# CONNECTEUR_1.net
KiCad netlist of a schematic drawn in Altium Designer
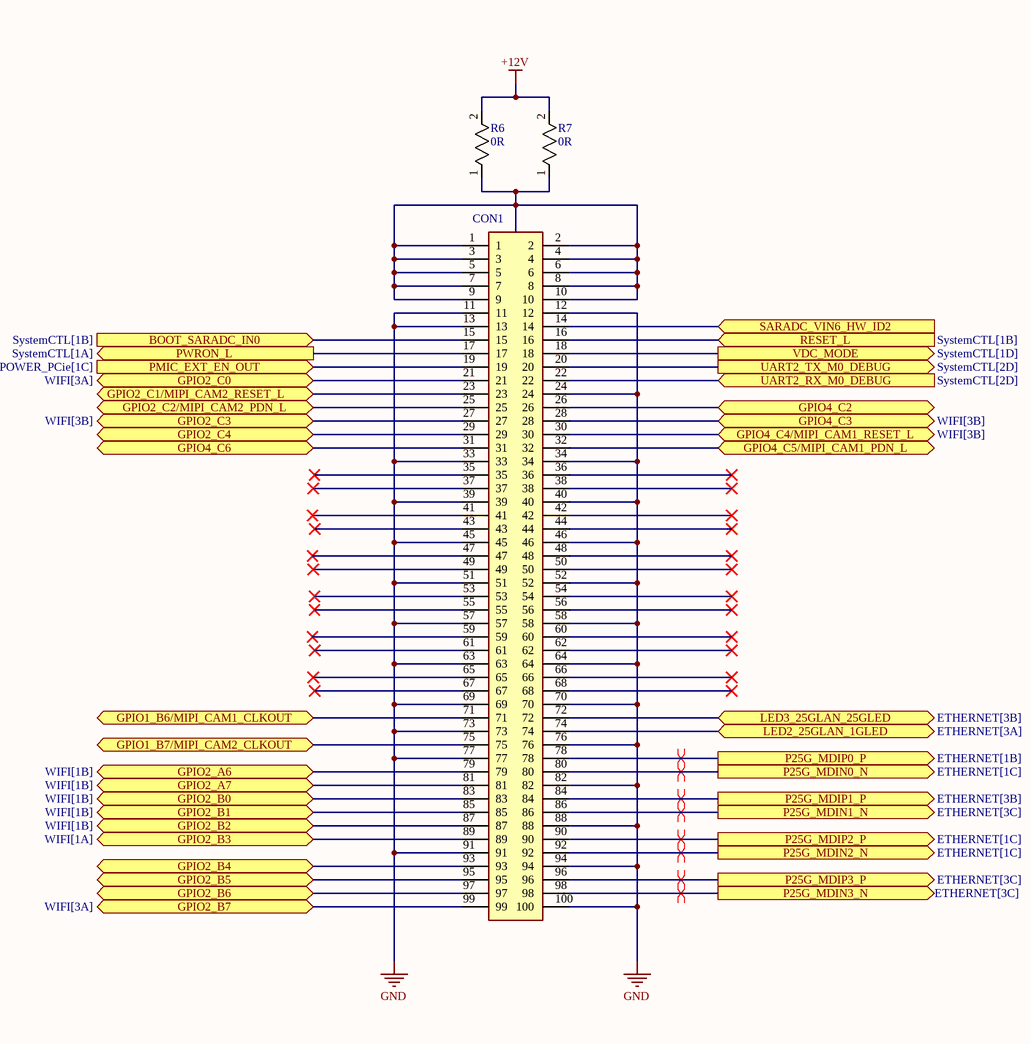
[diagram p0: CONNECTEUR_1.SchDoc, right]

(export (version "E")
  (design (tool "Eeschema 10.0.6"))
  (components
    (comp (ref "CON1")
      (value "DF40HC")
      (footprint "SamacSys:DF40HC30100DS04V51")
      (description "Stacking Board Connector, DF40 Series, Receptacle, 0.4 mm, 100, Surface Mount, G")
      (fields
        (field (name "MANUFACTURER_PART_NUMBER") "DF40HC(3.0)-100DS-0.4V(51")
        (field (name "MOUSER PART NUMBER") "798-DF40HC30100DS451")
      )
      (libsource (lib "SamacSys") (part "DF40HC(3.0)-100DS-0.4V(51)"))
    )
    (comp (ref "R6")
      (value "0R")
      (footprint "SamacSys:ERJ3EKF1000V")
      (description "Zero Ohm Resistor, Jumper, 0603 [1608 Metric], Thick Film, 100 mW, 1 A, Surface Mount")
      (fields
        (field (name "MANUFACTURER_PART_NUMBER") "ERJ-3GEY0R00V")
        (field (name "MOUSER PART NUMBER") "667-ERJ-3GEY0R00V")
      )
      (libsource (lib "SamacSys") (part "ERJ-3GEY0R00V"))
    )
    (comp (ref "R7")
      (value "0R")
      (footprint "SamacSys:ERJ3EKF1000V")
      (description "Zero Ohm Resistor, Jumper, 0603 [1608 Metric], Thick Film, 100 mW, 1 A, Surface Mount")
      (fields
        (field (name "MANUFACTURER_PART_NUMBER") "ERJ-3GEY0R00V")
        (field (name "MOUSER PART NUMBER") "667-ERJ-3GEY0R00V")
      )
      (libsource (lib "SamacSys") (part "ERJ-3GEY0R00V"))
    )
  )
  (nets
    (net (code "1") (name "+12V") (class "Default")
      (node (ref "R6") (pin "2") (pinfunction "2_2") (pintype "passive"))
      (node (ref "R7") (pin "2") (pinfunction "2_2") (pintype "passive"))
    )
    (net (code "2") (name "/BOOT_SARADC_IN0") (class "Default")
      (node (ref "CON1") (pin "15") (pinfunction "15_15") (pintype "passive"))
    )
    (net (code "3") (name "/GPIO1_B6{slash}MIPI_CAM1_CLKOUT") (class "Default")
      (node (ref "CON1") (pin "71") (pinfunction "71_71") (pintype "passive"))
    )
    (net (code "4") (name "/GPIO1_B7{slash}MIPI_CAM2_CLKOUT") (class "Default")
      (node (ref "CON1") (pin "75") (pinfunction "75_75") (pintype "passive"))
    )
    (net (code "5") (name "/GPIO2_A6") (class "Default")
      (node (ref "CON1") (pin "79") (pinfunction "79_79") (pintype "passive"))
    )
    (net (code "6") (name "/GPIO2_A7") (class "Default")
      (node (ref "CON1") (pin "81") (pinfunction "81_81") (pintype "passive"))
    )
    (net (code "7") (name "/GPIO2_B0") (class "Default")
      (node (ref "CON1") (pin "83") (pinfunction "83_83") (pintype "passive"))
    )
    (net (code "8") (name "/GPIO2_B1") (class "Default")
      (node (ref "CON1") (pin "85") (pinfunction "85_85") (pintype "passive"))
    )
    (net (code "9") (name "/GPIO2_B2") (class "Default")
      (node (ref "CON1") (pin "87") (pinfunction "87_87") (pintype "passive"))
    )
    (net (code "10") (name "/GPIO2_B3") (class "Default")
      (node (ref "CON1") (pin "89") (pinfunction "89_89") (pintype "passive"))
    )
    (net (code "11") (name "/GPIO2_B4") (class "Default")
      (node (ref "CON1") (pin "93") (pinfunction "93_93") (pintype "passive"))
    )
    (net (code "12") (name "/GPIO2_B5") (class "Default")
      (node (ref "CON1") (pin "95") (pinfunction "95_95") (pintype "passive"))
    )
    (net (code "13") (name "/GPIO2_B6") (class "Default")
      (node (ref "CON1") (pin "97") (pinfunction "97_97") (pintype "passive"))
    )
    (net (code "14") (name "/GPIO2_B7") (class "Default")
      (node (ref "CON1") (pin "99") (pinfunction "99_99") (pintype "passive"))
    )
    (net (code "15") (name "/GPIO2_C0") (class "Default")
      (node (ref "CON1") (pin "21") (pinfunction "21_21") (pintype "passive"))
    )
    (net (code "16") (name "/GPIO2_C1{slash}MIPI_CAM2_RESET_L") (class "Default")
      (node (ref "CON1") (pin "23") (pinfunction "23_23") (pintype "passive"))
    )
    (net (code "17") (name "/GPIO2_C2{slash}MIPI_CAM2_PDN_L") (class "Default")
      (node (ref "CON1") (pin "25") (pinfunction "25_25") (pintype "passive"))
    )
    (net (code "18") (name "/GPIO2_C3") (class "Default")
      (node (ref "CON1") (pin "27") (pinfunction "27_27") (pintype "passive"))
    )
    (net (code "19") (name "/GPIO2_C4") (class "Default")
      (node (ref "CON1") (pin "29") (pinfunction "29_29") (pintype "passive"))
    )
    (net (code "20") (name "/GPIO4_C2") (class "Default")
      (node (ref "CON1") (pin "26") (pinfunction "26_26") (pintype "passive"))
    )
    (net (code "21") (name "/GPIO4_C3") (class "Default")
      (node (ref "CON1") (pin "28") (pinfunction "28_28") (pintype "passive"))
    )
    (net (code "22") (name "/GPIO4_C4{slash}MIPI_CAM1_RESET_L") (class "Default")
      (node (ref "CON1") (pin "30") (pinfunction "30_30") (pintype "passive"))
    )
    (net (code "23") (name "/GPIO4_C5{slash}MIPI_CAM1_PDN_L") (class "Default")
      (node (ref "CON1") (pin "32") (pinfunction "32_32") (pintype "passive"))
    )
    (net (code "24") (name "/GPIO4_C6") (class "Default")
      (node (ref "CON1") (pin "31") (pinfunction "31_31") (pintype "passive"))
    )
    (net (code "25") (name "/LED2_25GLAN_1GLED") (class "Default")
      (node (ref "CON1") (pin "74") (pinfunction "74_74") (pintype "passive"))
    )
    (net (code "26") (name "/LED3_25GLAN_25GLED") (class "Default")
      (node (ref "CON1") (pin "72") (pinfunction "72_72") (pintype "passive"))
    )
    (net (code "27") (name "/P25G_MDIN0_N") (class "Default")
      (node (ref "CON1") (pin "80") (pinfunction "80_80") (pintype "passive"))
    )
    (net (code "28") (name "/P25G_MDIN1_N") (class "Default")
      (node (ref "CON1") (pin "86") (pinfunction "86_86") (pintype "passive"))
    )
    (net (code "29") (name "/P25G_MDIN2_N") (class "Default")
      (node (ref "CON1") (pin "92") (pinfunction "92_92") (pintype "passive"))
    )
    (net (code "30") (name "/P25G_MDIN3_N") (class "Default")
      (node (ref "CON1") (pin "98") (pinfunction "98_98") (pintype "passive"))
    )
    (net (code "31") (name "/P25G_MDIP0_P") (class "Default")
      (node (ref "CON1") (pin "78") (pinfunction "78_78") (pintype "passive"))
    )
    (net (code "32") (name "/P25G_MDIP1_P") (class "Default")
      (node (ref "CON1") (pin "84") (pinfunction "84_84") (pintype "passive"))
    )
    (net (code "33") (name "/P25G_MDIP2_P") (class "Default")
      (node (ref "CON1") (pin "90") (pinfunction "90_90") (pintype "passive"))
    )
    (net (code "34") (name "/P25G_MDIP3_P") (class "Default")
      (node (ref "CON1") (pin "96") (pinfunction "96_96") (pintype "passive"))
    )
    (net (code "35") (name "/PMIC_EXT_EN_OUT") (class "Default")
      (node (ref "CON1") (pin "19") (pinfunction "19_19") (pintype "passive"))
    )
    (net (code "36") (name "/PWRON_L") (class "Default")
      (node (ref "CON1") (pin "17") (pinfunction "17_17") (pintype "passive"))
    )
    (net (code "37") (name "/RESET_L") (class "Default")
      (node (ref "CON1") (pin "16") (pinfunction "16_16") (pintype "passive"))
    )
    (net (code "38") (name "/SARADC_VIN6_HW_ID2") (class "Default")
      (node (ref "CON1") (pin "14") (pinfunction "14_14") (pintype "passive"))
    )
    (net (code "39") (name "/UART2_RX_M0_DEBUG") (class "Default")
      (node (ref "CON1") (pin "22") (pinfunction "22_22") (pintype "passive"))
    )
    (net (code "40") (name "/UART2_TX_M0_DEBUG") (class "Default")
      (node (ref "CON1") (pin "20") (pinfunction "20_20") (pintype "passive"))
    )
    (net (code "41") (name "/VDC_MODE") (class "Default")
      (node (ref "CON1") (pin "18") (pinfunction "18_18") (pintype "passive"))
    )
    (net (code "42") (name "GND") (class "Default")
      (node (ref "CON1") (pin "100") (pinfunction "100_100") (pintype "passive"))
      (node (ref "CON1") (pin "11") (pinfunction "11_11") (pintype "passive"))
      (node (ref "CON1") (pin "12") (pinfunction "12_12") (pintype "passive"))
      (node (ref "CON1") (pin "13") (pinfunction "13_13") (pintype "passive"))
      (node (ref "CON1") (pin "24") (pinfunction "24_24") (pintype "passive"))
      (node (ref "CON1") (pin "33") (pinfunction "33_33") (pintype "passive"))
      (node (ref "CON1") (pin "34") (pinfunction "34_34") (pintype "passive"))
      (node (ref "CON1") (pin "39") (pinfunction "39_39") (pintype "passive"))
      (node (ref "CON1") (pin "40") (pinfunction "40_40") (pintype "passive"))
      (node (ref "CON1") (pin "45") (pinfunction "45_45") (pintype "passive"))
      (node (ref "CON1") (pin "46") (pinfunction "46_46") (pintype "passive"))
      (node (ref "CON1") (pin "51") (pinfunction "51_51") (pintype "passive"))
      (node (ref "CON1") (pin "52") (pinfunction "52_52") (pintype "passive"))
      (node (ref "CON1") (pin "57") (pinfunction "57_57") (pintype "passive"))
      (node (ref "CON1") (pin "58") (pinfunction "58_58") (pintype "passive"))
      (node (ref "CON1") (pin "63") (pinfunction "63_63") (pintype "passive"))
      (node (ref "CON1") (pin "64") (pinfunction "64_64") (pintype "passive"))
      (node (ref "CON1") (pin "69") (pinfunction "69_69") (pintype "passive"))
      (node (ref "CON1") (pin "70") (pinfunction "70_70") (pintype "passive"))
      (node (ref "CON1") (pin "73") (pinfunction "73_73") (pintype "passive"))
      (node (ref "CON1") (pin "76") (pinfunction "76_76") (pintype "passive"))
      (node (ref "CON1") (pin "77") (pinfunction "77_77") (pintype "passive"))
      (node (ref "CON1") (pin "82") (pinfunction "82_82") (pintype "passive"))
      (node (ref "CON1") (pin "88") (pinfunction "88_88") (pintype "passive"))
      (node (ref "CON1") (pin "91") (pinfunction "91_91") (pintype "passive"))
      (node (ref "CON1") (pin "94") (pinfunction "94_94") (pintype "passive"))
    )
    (net (code "43") (name "Net-(CON1-Pad1)") (class "Default")
      (node (ref "CON1") (pin "1") (pinfunction "1_1") (pintype "passive"))
      (node (ref "CON1") (pin "10") (pinfunction "10_10") (pintype "passive"))
      (node (ref "CON1") (pin "2") (pinfunction "2_2") (pintype "passive"))
      (node (ref "CON1") (pin "3") (pinfunction "3_3") (pintype "passive"))
      (node (ref "CON1") (pin "4") (pinfunction "4_4") (pintype "passive"))
      (node (ref "CON1") (pin "5") (pinfunction "5_5") (pintype "passive"))
      (node (ref "CON1") (pin "6") (pinfunction "6_6") (pintype "passive"))
      (node (ref "CON1") (pin "7") (pinfunction "7_7") (pintype "passive"))
      (node (ref "CON1") (pin "8") (pinfunction "8_8") (pintype "passive"))
      (node (ref "CON1") (pin "9") (pinfunction "9_9") (pintype "passive"))
      (node (ref "R6") (pin "1") (pinfunction "1_1") (pintype "passive"))
      (node (ref "R7") (pin "1") (pinfunction "1_1") (pintype "passive"))
    )
    (net (code "44") (name "unconnected-(CON1-Pad35)") (class "Default")
      (node (ref "CON1") (pin "35") (pinfunction "35_35") (pintype "passive+no_connect"))
    )
    (net (code "45") (name "unconnected-(CON1-Pad36)") (class "Default")
      (node (ref "CON1") (pin "36") (pinfunction "36_36") (pintype "passive+no_connect"))
    )
    (net (code "46") (name "unconnected-(CON1-Pad37)") (class "Default")
      (node (ref "CON1") (pin "37") (pinfunction "37_37") (pintype "passive+no_connect"))
    )
    (net (code "47") (name "unconnected-(CON1-Pad38)") (class "Default")
      (node (ref "CON1") (pin "38") (pinfunction "38_38") (pintype "passive+no_connect"))
    )
    (net (code "48") (name "unconnected-(CON1-Pad41)") (class "Default")
      (node (ref "CON1") (pin "41") (pinfunction "41_41") (pintype "passive+no_connect"))
    )
    (net (code "49") (name "unconnected-(CON1-Pad42)") (class "Default")
      (node (ref "CON1") (pin "42") (pinfunction "42_42") (pintype "passive+no_connect"))
    )
    (net (code "50") (name "unconnected-(CON1-Pad43)") (class "Default")
      (node (ref "CON1") (pin "43") (pinfunction "43_43") (pintype "passive+no_connect"))
    )
    (net (code "51") (name "unconnected-(CON1-Pad44)") (class "Default")
      (node (ref "CON1") (pin "44") (pinfunction "44_44") (pintype "passive+no_connect"))
    )
    (net (code "52") (name "unconnected-(CON1-Pad47)") (class "Default")
      (node (ref "CON1") (pin "47") (pinfunction "47_47") (pintype "passive+no_connect"))
    )
    (net (code "53") (name "unconnected-(CON1-Pad48)") (class "Default")
      (node (ref "CON1") (pin "48") (pinfunction "48_48") (pintype "passive+no_connect"))
    )
    (net (code "54") (name "unconnected-(CON1-Pad49)") (class "Default")
      (node (ref "CON1") (pin "49") (pinfunction "49_49") (pintype "passive+no_connect"))
    )
    (net (code "55") (name "unconnected-(CON1-Pad50)") (class "Default")
      (node (ref "CON1") (pin "50") (pinfunction "50_50") (pintype "passive+no_connect"))
    )
    (net (code "56") (name "unconnected-(CON1-Pad53)") (class "Default")
      (node (ref "CON1") (pin "53") (pinfunction "53_53") (pintype "passive+no_connect"))
    )
    (net (code "57") (name "unconnected-(CON1-Pad54)") (class "Default")
      (node (ref "CON1") (pin "54") (pinfunction "54_54") (pintype "passive+no_connect"))
    )
    (net (code "58") (name "unconnected-(CON1-Pad55)") (class "Default")
      (node (ref "CON1") (pin "55") (pinfunction "55_55") (pintype "passive+no_connect"))
    )
    (net (code "59") (name "unconnected-(CON1-Pad56)") (class "Default")
      (node (ref "CON1") (pin "56") (pinfunction "56_56") (pintype "passive+no_connect"))
    )
    (net (code "60") (name "unconnected-(CON1-Pad59)") (class "Default")
      (node (ref "CON1") (pin "59") (pinfunction "59_59") (pintype "passive+no_connect"))
    )
    (net (code "61") (name "unconnected-(CON1-Pad60)") (class "Default")
      (node (ref "CON1") (pin "60") (pinfunction "60_60") (pintype "passive+no_connect"))
    )
    (net (code "62") (name "unconnected-(CON1-Pad61)") (class "Default")
      (node (ref "CON1") (pin "61") (pinfunction "61_61") (pintype "passive+no_connect"))
    )
    (net (code "63") (name "unconnected-(CON1-Pad62)") (class "Default")
      (node (ref "CON1") (pin "62") (pinfunction "62_62") (pintype "passive+no_connect"))
    )
    (net (code "64") (name "unconnected-(CON1-Pad65)") (class "Default")
      (node (ref "CON1") (pin "65") (pinfunction "65_65") (pintype "passive+no_connect"))
    )
    (net (code "65") (name "unconnected-(CON1-Pad66)") (class "Default")
      (node (ref "CON1") (pin "66") (pinfunction "66_66") (pintype "passive+no_connect"))
    )
    (net (code "66") (name "unconnected-(CON1-Pad67)") (class "Default")
      (node (ref "CON1") (pin "67") (pinfunction "67_67") (pintype "passive+no_connect"))
    )
    (net (code "67") (name "unconnected-(CON1-Pad68)") (class "Default")
      (node (ref "CON1") (pin "68") (pinfunction "68_68") (pintype "passive+no_connect"))
    )
  )
)
